# ESP32_WROOM2.net
KiCad netlist of a schematic drawn in Altium Designer
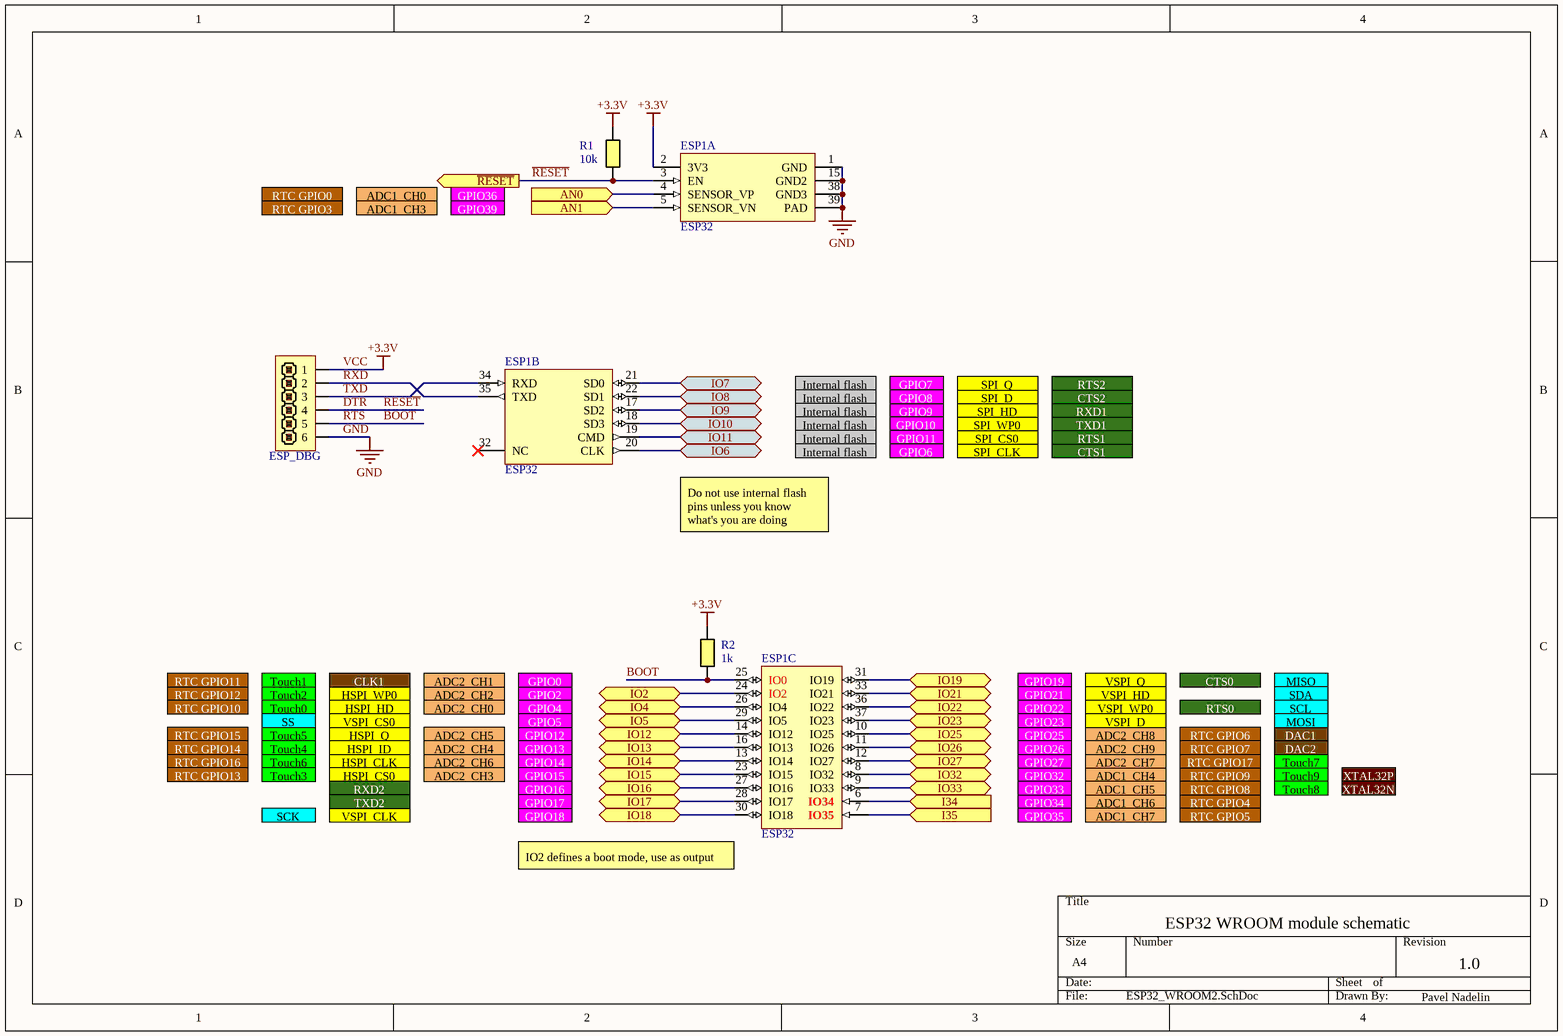
[diagram p0: ESP32_WROOM2.SchDoc]

(export (version "E")
  (design (tool "Eeschema 10.0.6"))
  (components
    (comp (ref "ESP1")
      (value "ESP32")
      (footprint "ESP32-WROOM")
      (description "ESP32-WROOM-32 is a powerful, generic Wi-Fi+BT+BLE MCU module")
      (libsource (lib "Modules") (part "ESP32S"))
    )
    (comp (ref "ESP_DBG")
      (value "PIN HEADER 1x6")
      (footprint "PIN HEADER SINGLE 6")
      (libsource (lib "Connectors_DEBUG_Testpoints") (part "PIN HEADER 2.54 1x6"))
    )
    (comp (ref "R1")
      (value "10k")
      (footprint "RESC0603(1608)_N")
      (description "Resistor Medium Density")
      (libsource (lib "Discrete_Passive_RCL") (part "Resistor M"))
    )
    (comp (ref "R2")
      (value "1k")
      (footprint "RESC0603(1608)_N")
      (description "Resistor Medium Density")
      (libsource (lib "Discrete_Passive_RCL") (part "Resistor M"))
    )
  )
  (nets
    (net (code "1") (name "+3.3V") (class "Default")
      (node (ref "ESP1") (pin "2") (pinfunction "3V3_2") (pintype "power_in"))
      (node (ref "ESP_DBG") (pin "1") (pinfunction "1_1") (pintype "passive"))
      (node (ref "R1") (pin "1") (pinfunction "1_1") (pintype "passive"))
      (node (ref "R2") (pin "1") (pinfunction "1_1") (pintype "passive"))
    )
    (net (code "2") (name "/AN0") (class "Default")
      (node (ref "ESP1") (pin "4") (pinfunction "SENSOR_VP_4") (pintype "input"))
    )
    (net (code "3") (name "/AN1") (class "Default")
      (node (ref "ESP1") (pin "5") (pinfunction "SENSOR_VN_5") (pintype "input"))
    )
    (net (code "4") (name "/BOOT") (class "Default")
      (node (ref "ESP1") (pin "25") (pinfunction "IO0_25") (pintype "bidirectional"))
      (node (ref "ESP_DBG") (pin "5") (pinfunction "5_5") (pintype "passive"))
      (node (ref "R2") (pin "2") (pinfunction "2_2") (pintype "passive"))
    )
    (net (code "5") (name "/DTR") (class "Default")
      (node (ref "ESP1") (pin "3") (pinfunction "EN_3") (pintype "input"))
      (node (ref "ESP_DBG") (pin "4") (pinfunction "4_4") (pintype "passive"))
      (node (ref "R1") (pin "2") (pinfunction "2_2") (pintype "passive"))
    )
    (net (code "6") (name "/I34") (class "Default")
      (node (ref "ESP1") (pin "6") (pinfunction "IO34_6") (pintype "input"))
    )
    (net (code "7") (name "/I35") (class "Default")
      (node (ref "ESP1") (pin "7") (pinfunction "IO35_7") (pintype "input"))
    )
    (net (code "8") (name "/IO2") (class "Default")
      (node (ref "ESP1") (pin "24") (pinfunction "IO2_24") (pintype "bidirectional"))
    )
    (net (code "9") (name "/IO4") (class "Default")
      (node (ref "ESP1") (pin "26") (pinfunction "IO4_26") (pintype "bidirectional"))
    )
    (net (code "10") (name "/IO5") (class "Default")
      (node (ref "ESP1") (pin "29") (pinfunction "IO5_29") (pintype "bidirectional"))
    )
    (net (code "11") (name "/IO6") (class "Default")
      (node (ref "ESP1") (pin "20") (pinfunction "CLK_20") (pintype "output"))
    )
    (net (code "12") (name "/IO7") (class "Default")
      (node (ref "ESP1") (pin "21") (pinfunction "SD0_21") (pintype "bidirectional"))
    )
    (net (code "13") (name "/IO8") (class "Default")
      (node (ref "ESP1") (pin "22") (pinfunction "SD1_22") (pintype "bidirectional"))
    )
    (net (code "14") (name "/IO9") (class "Default")
      (node (ref "ESP1") (pin "17") (pinfunction "SD2_17") (pintype "bidirectional"))
    )
    (net (code "15") (name "/IO10") (class "Default")
      (node (ref "ESP1") (pin "18") (pinfunction "SD3_18") (pintype "bidirectional"))
    )
    (net (code "16") (name "/IO11") (class "Default")
      (node (ref "ESP1") (pin "19") (pinfunction "CMD_19") (pintype "output"))
    )
    (net (code "17") (name "/IO12") (class "Default")
      (node (ref "ESP1") (pin "14") (pinfunction "IO12_14") (pintype "bidirectional"))
    )
    (net (code "18") (name "/IO13") (class "Default")
      (node (ref "ESP1") (pin "16") (pinfunction "IO13_16") (pintype "bidirectional"))
    )
    (net (code "19") (name "/IO14") (class "Default")
      (node (ref "ESP1") (pin "13") (pinfunction "IO14_13") (pintype "bidirectional"))
    )
    (net (code "20") (name "/IO15") (class "Default")
      (node (ref "ESP1") (pin "23") (pinfunction "IO15_23") (pintype "bidirectional"))
    )
    (net (code "21") (name "/IO16") (class "Default")
      (node (ref "ESP1") (pin "27") (pinfunction "IO16_27") (pintype "bidirectional"))
    )
    (net (code "22") (name "/IO17") (class "Default")
      (node (ref "ESP1") (pin "28") (pinfunction "IO17_28") (pintype "bidirectional"))
    )
    (net (code "23") (name "/IO18") (class "Default")
      (node (ref "ESP1") (pin "30") (pinfunction "IO18_30") (pintype "bidirectional"))
    )
    (net (code "24") (name "/IO19") (class "Default")
      (node (ref "ESP1") (pin "31") (pinfunction "IO19_31") (pintype "bidirectional"))
    )
    (net (code "25") (name "/IO21") (class "Default")
      (node (ref "ESP1") (pin "33") (pinfunction "IO21_33") (pintype "bidirectional"))
    )
    (net (code "26") (name "/IO22") (class "Default")
      (node (ref "ESP1") (pin "36") (pinfunction "IO22_36") (pintype "bidirectional"))
    )
    (net (code "27") (name "/IO23") (class "Default")
      (node (ref "ESP1") (pin "37") (pinfunction "IO23_37") (pintype "bidirectional"))
    )
    (net (code "28") (name "/IO25") (class "Default")
      (node (ref "ESP1") (pin "10") (pinfunction "IO25_10") (pintype "bidirectional"))
    )
    (net (code "29") (name "/IO26") (class "Default")
      (node (ref "ESP1") (pin "11") (pinfunction "IO26_11") (pintype "bidirectional"))
    )
    (net (code "30") (name "/IO27") (class "Default")
      (node (ref "ESP1") (pin "12") (pinfunction "IO27_12") (pintype "bidirectional"))
    )
    (net (code "31") (name "/IO32") (class "Default")
      (node (ref "ESP1") (pin "8") (pinfunction "IO32_8") (pintype "bidirectional"))
    )
    (net (code "32") (name "/IO33") (class "Default")
      (node (ref "ESP1") (pin "9") (pinfunction "IO33_9") (pintype "bidirectional"))
    )
    (net (code "33") (name "/RXD") (class "Default")
      (node (ref "ESP1") (pin "35") (pinfunction "TXD_35") (pintype "output"))
      (node (ref "ESP_DBG") (pin "2") (pinfunction "2_2") (pintype "passive"))
    )
    (net (code "34") (name "/TXD") (class "Default")
      (node (ref "ESP1") (pin "34") (pinfunction "RXD_34") (pintype "input"))
      (node (ref "ESP_DBG") (pin "3") (pinfunction "3_3") (pintype "passive"))
    )
    (net (code "35") (name "GND") (class "Default")
      (node (ref "ESP1") (pin "1") (pinfunction "GND_1") (pintype "power_in"))
      (node (ref "ESP1") (pin "15") (pinfunction "GND2_15") (pintype "power_in"))
      (node (ref "ESP1") (pin "38") (pinfunction "GND3_38") (pintype "power_in"))
      (node (ref "ESP1") (pin "39") (pinfunction "PAD_39") (pintype "power_in"))
      (node (ref "ESP_DBG") (pin "6") (pinfunction "6_6") (pintype "passive"))
    )
    (net (code "36") (name "unconnected-(ESP1B-NC-Pad32)") (class "Default")
      (node (ref "ESP1") (pin "32") (pinfunction "NC_32") (pintype "passive+no_connect"))
    )
  )
)
